# DMB.net
KiCad netlist of a schematic drawn in Altium Designer
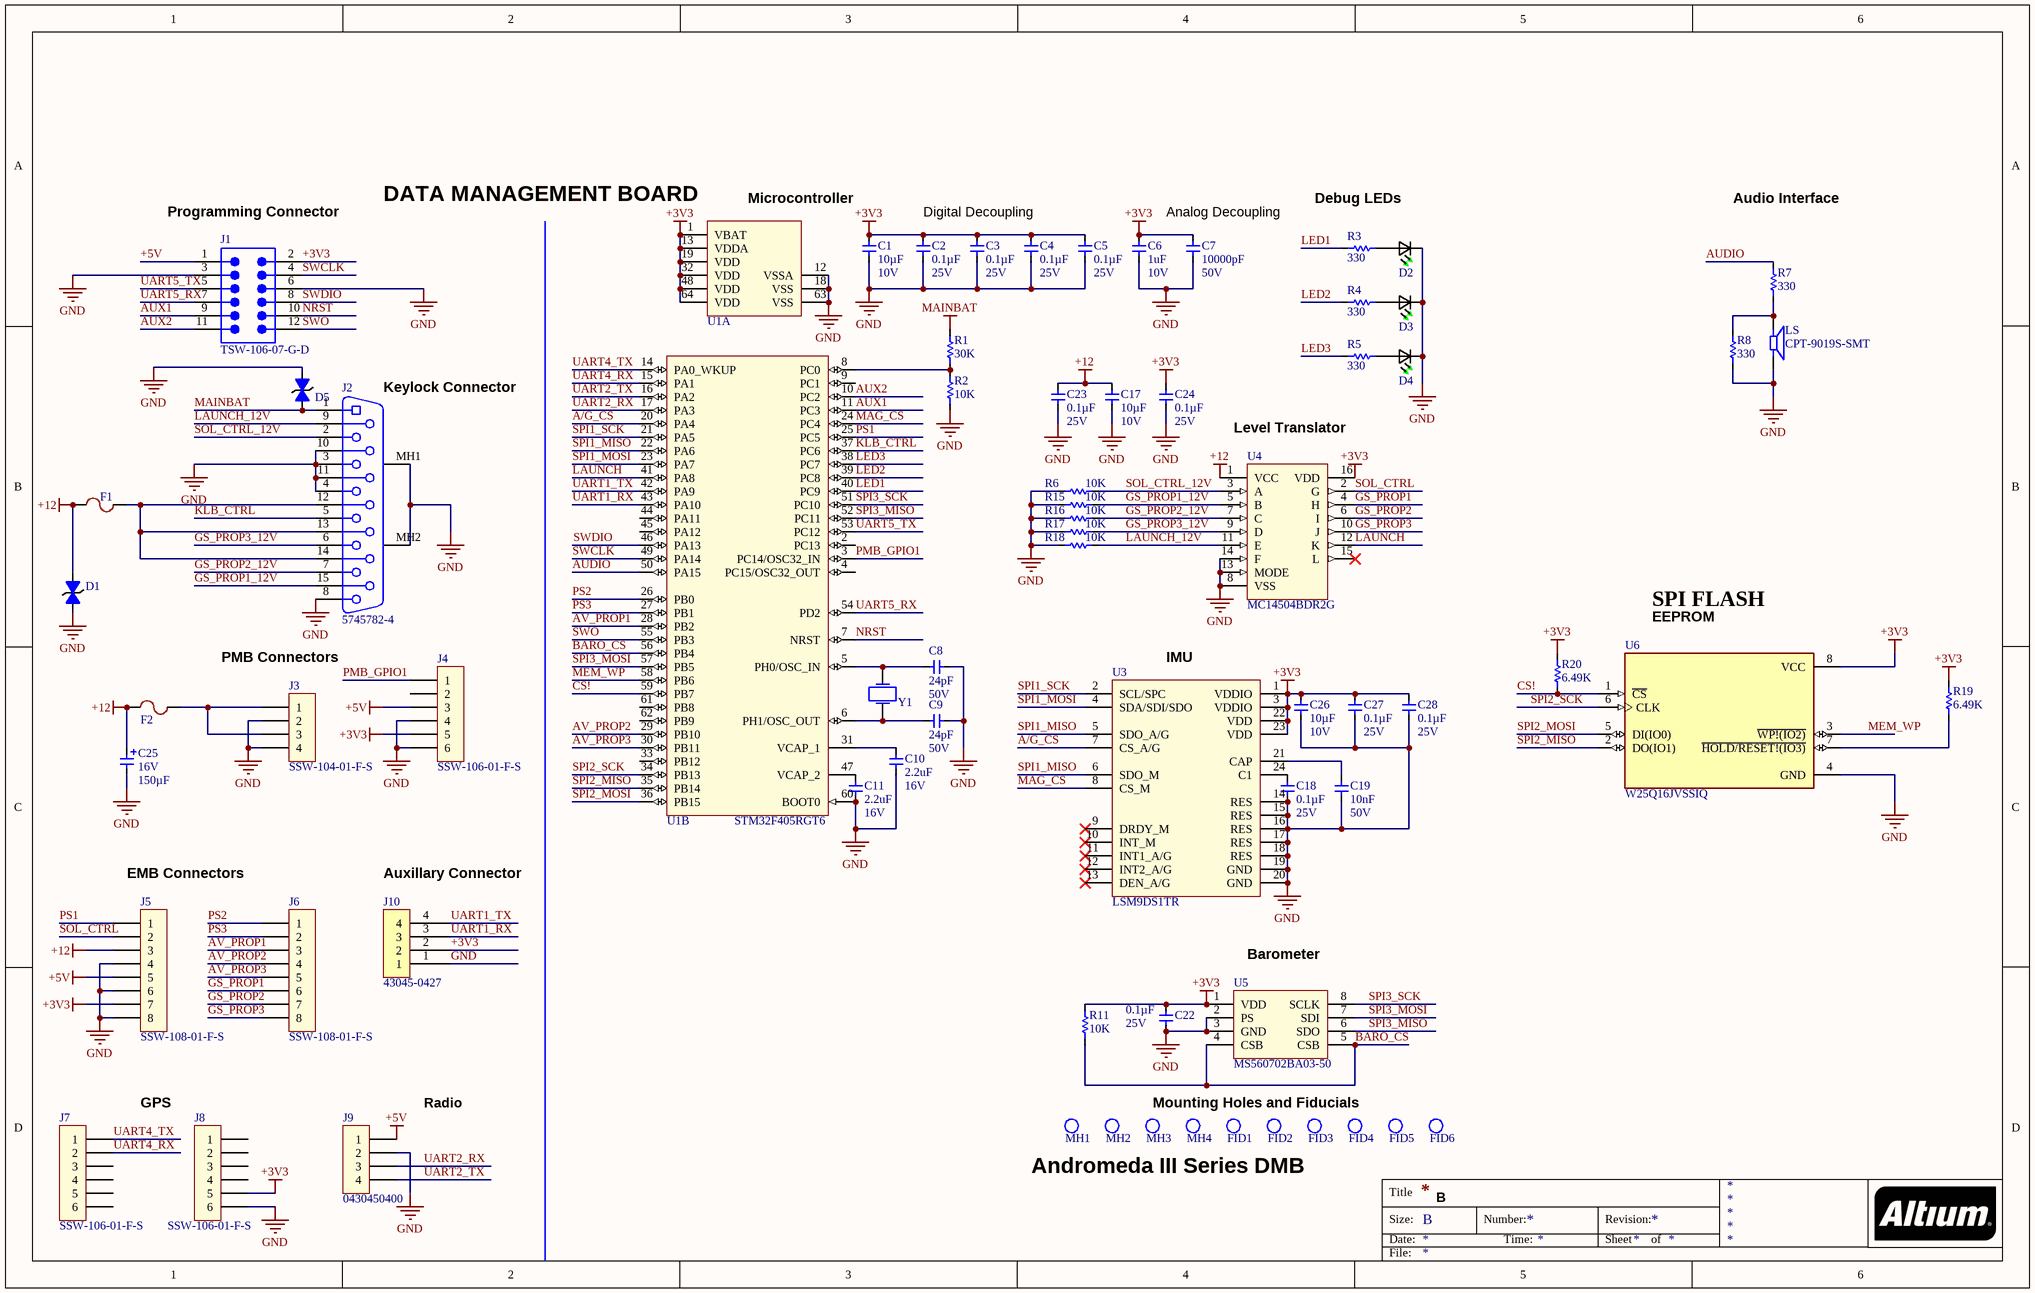
[diagram p0: DMB.SchDoc]

(export (version "E")
  (design (tool "Eeschema 10.0.6"))
  (components
    (comp (ref "C1")
      (value "CL10A106MP8NNNC")
      (footprint "0603[1608]")
      (description "CAP CER 10UF 10V X5R 0603")
      (fields
        (field (name "MANUFACTURER") "Samsung Electro-Mechanics")
        (field (name "TOLERANCE") "±20%")
        (field (name "CAPACITANCE") "10µF")
        (field (name "VOLTAGE - RATED") "10V")
      )
      (libsource (lib "SOARSchematics") (part "CL10A106MP8NNNC"))
    )
    (comp (ref "C2")
      (value "CGA3E2X7R1E104K080AA")
      (footprint "0603[1608]")
      (description "CAP CER 0.1UF 25V X7R 0603")
      (fields
        (field (name "MANUFACTURER") "TDK Corporation")
        (field (name "TOLERANCE") "±10%")
        (field (name "CAPACITANCE") "0.1µF")
        (field (name "VOLTAGE - RATED") "25V")
      )
      (libsource (lib "SOARSchematics") (part "CGA3E2X7R1E104K080AA"))
    )
    (comp (ref "C3")
      (value "CGA3E2X7R1E104K080AA")
      (footprint "0603[1608]")
      (description "CAP CER 0.1UF 25V X7R 0603")
      (fields
        (field (name "MANUFACTURER") "TDK Corporation")
        (field (name "TOLERANCE") "±10%")
        (field (name "CAPACITANCE") "0.1µF")
        (field (name "VOLTAGE - RATED") "25V")
      )
      (libsource (lib "SOARSchematics") (part "CGA3E2X7R1E104K080AA"))
    )
    (comp (ref "C4")
      (value "CGA3E2X7R1E104K080AA")
      (footprint "0603[1608]")
      (description "CAP CER 0.1UF 25V X7R 0603")
      (fields
        (field (name "MANUFACTURER") "TDK Corporation")
        (field (name "TOLERANCE") "±10%")
        (field (name "CAPACITANCE") "0.1µF")
        (field (name "VOLTAGE - RATED") "25V")
      )
      (libsource (lib "SOARSchematics") (part "CGA3E2X7R1E104K080AA"))
    )
    (comp (ref "C5")
      (value "CGA3E2X7R1E104K080AA")
      (footprint "0603[1608]")
      (description "CAP CER 0.1UF 25V X7R 0603")
      (fields
        (field (name "MANUFACTURER") "TDK Corporation")
        (field (name "TOLERANCE") "±10%")
        (field (name "CAPACITANCE") "0.1µF")
        (field (name "VOLTAGE - RATED") "25V")
      )
      (libsource (lib "SOARSchematics") (part "CGA3E2X7R1E104K080AA"))
    )
    (comp (ref "C6")
      (value "CL10A105KP8NNNC")
      (footprint "0603[1608]")
      (description "CAP CER 1UF 10V X5R 0603")
      (fields
        (field (name "MANUFACTURER") "Samsung Electro-Mechanics")
        (field (name "TOLERANCE") "±10%")
        (field (name "CAPACITANCE") "1uF")
        (field (name "VOLTAGE - RATED") "10V")
      )
      (libsource (lib "SOARSchematics") (part "CL10A105KP8NNNC"))
    )
    (comp (ref "C7")
      (value "CGA3E2X7R1H103K080AA")
      (footprint "0603[1608]")
      (description "CAP CER 10000PF 50V X7R 0603")
      (fields
        (field (name "MANUFACTURER") "TDK Corporation")
        (field (name "TOLERANCE") "±10%")
        (field (name "CAPACITANCE") "10000pF")
        (field (name "VOLTAGE - RATED") "50V")
      )
      (libsource (lib "SOARSchematics") (part "CGA3E2X7R1H103K080AA"))
    )
    (comp (ref "C8")
      (value "06035A240JAT2A")
      (footprint "0603[1608]")
      (description "CAP CER 24PF 50V NP0 0603")
      (fields
        (field (name "MANUFACTURER") "AVX Corporation")
        (field (name "TOLERANCE") "±5%")
        (field (name "CAPACITANCE") "24pF")
        (field (name "VOLTAGE - RATED") "50V")
      )
      (libsource (lib "SOARSchematics") (part "06035A240JAT2A"))
    )
    (comp (ref "C9")
      (value "06035A240JAT2A")
      (footprint "0603[1608]")
      (description "CAP CER 24PF 50V NP0 0603")
      (fields
        (field (name "MANUFACTURER") "AVX Corporation")
        (field (name "TOLERANCE") "±5%")
        (field (name "CAPACITANCE") "24pF")
        (field (name "VOLTAGE - RATED") "50V")
      )
      (libsource (lib "SOARSchematics") (part "06035A240JAT2A"))
    )
    (comp (ref "C10")
      (value "C1608X5R1C225K080AB")
      (footprint "0603[1608]")
      (description "CAP CER 2.2UF 16V X5R 0603")
      (fields
        (field (name "MANUFACTURER") "TDK Corporation")
        (field (name "TOLERANCE") "±10%")
        (field (name "CAPACITANCE") "2.2uF")
        (field (name "VOLTAGE - RATED") "16V")
      )
      (libsource (lib "SOARSchematics") (part "C1608X5R1C225K080AB"))
    )
    (comp (ref "C11")
      (value "C1608X5R1C225K080AB")
      (footprint "0603[1608]")
      (description "CAP CER 2.2UF 16V X5R 0603")
      (fields
        (field (name "MANUFACTURER") "TDK Corporation")
        (field (name "TOLERANCE") "±10%")
        (field (name "CAPACITANCE") "2.2uF")
        (field (name "VOLTAGE - RATED") "16V")
      )
      (libsource (lib "SOARSchematics") (part "C1608X5R1C225K080AB"))
    )
    (comp (ref "C17")
      (value "CL10A106MP8NNNC")
      (footprint "0603[1608]")
      (description "CAP CER 10UF 10V X5R 0603")
      (fields
        (field (name "MANUFACTURER") "Samsung Electro-Mechanics")
        (field (name "TOLERANCE") "±20%")
        (field (name "CAPACITANCE") "10µF")
        (field (name "VOLTAGE - RATED") "10V")
      )
      (libsource (lib "SOARSchematics") (part "CL10A106MP8NNNC"))
    )
    (comp (ref "C18")
      (value "CGA3E2X7R1E104K080AA")
      (footprint "0603[1608]")
      (description "CAP CER 0.1UF 25V X7R 0603")
      (fields
        (field (name "MANUFACTURER") "TDK Corporation")
        (field (name "TOLERANCE") "±10%")
        (field (name "CAPACITANCE") "0.1µF")
        (field (name "VOLTAGE - RATED") "25V")
      )
      (libsource (lib "SOARSchematics") (part "CGA3E2X7R1E104K080AA"))
    )
    (comp (ref "C19")
      (value "GRM1885C1H103JA01D")
      (footprint "0603[1608]")
      (description "CAP CER 10000PF 50V C0G/NP0 0603")
      (fields
        (field (name "MANUFACTURER") "Murata Electronics")
        (field (name "TOLERANCE") "±50%")
        (field (name "CAPACITANCE") "10nF")
        (field (name "VOLTAGE - RATED") "50V")
      )
      (libsource (lib "SOARSchematics") (part "GRM1885C1H103JA01D"))
    )
    (comp (ref "C22")
      (value "CGA3E2X7R1E104K080AA")
      (footprint "0603[1608]")
      (description "CAP CER 0.1UF 25V X7R 0603")
      (fields
        (field (name "MANUFACTURER") "TDK Corporation")
        (field (name "TOLERANCE") "±10%")
        (field (name "CAPACITANCE") "0.1µF")
        (field (name "VOLTAGE - RATED") "25V")
      )
      (libsource (lib "SOARSchematics") (part "CGA3E2X7R1E104K080AA"))
    )
    (comp (ref "C23")
      (value "CGA3E2X7R1E104K080AA")
      (footprint "0603[1608]")
      (description "CAP CER 0.1UF 25V X7R 0603")
      (fields
        (field (name "MANUFACTURER") "TDK Corporation")
        (field (name "TOLERANCE") "±10%")
        (field (name "CAPACITANCE") "0.1µF")
        (field (name "VOLTAGE - RATED") "25V")
      )
      (libsource (lib "SOARSchematics") (part "CGA3E2X7R1E104K080AA"))
    )
    (comp (ref "C24")
      (value "CGA3E2X7R1E104K080AA")
      (footprint "0603[1608]")
      (description "CAP CER 0.1UF 25V X7R 0603")
      (fields
        (field (name "MANUFACTURER") "TDK Corporation")
        (field (name "TOLERANCE") "±10%")
        (field (name "CAPACITANCE") "0.1µF")
        (field (name "VOLTAGE - RATED") "25V")
      )
      (libsource (lib "SOARSchematics") (part "CGA3E2X7R1E104K080AA"))
    )
    (comp (ref "C25")
      (value "TAJD157K016RNJ")
      (footprint "TAJD157K016RNJ")
      (description "CAP TANT 150UF 10% 16V 2917")
      (fields
        (field (name "MANUFACTURER") "AVX Corporation")
        (field (name "TOLERANCE") "±10%")
        (field (name "VOLTAGE - RATED") "16V")
        (field (name "CAPACITANCE") "150µF")
      )
      (libsource (lib "SOARSchematics") (part "TAJD157K016RNJ"))
    )
    (comp (ref "C26")
      (value "CL10A106MP8NNNC")
      (footprint "0603[1608]")
      (description "CAP CER 10UF 10V X5R 0603")
      (fields
        (field (name "MANUFACTURER") "Samsung Electro-Mechanics")
        (field (name "TOLERANCE") "±20%")
        (field (name "CAPACITANCE") "10µF")
        (field (name "VOLTAGE - RATED") "10V")
      )
      (libsource (lib "SOARSchematics") (part "CL10A106MP8NNNC"))
    )
    (comp (ref "C27")
      (value "CGA3E2X7R1E104K080AA")
      (footprint "0603[1608]")
      (description "CAP CER 0.1UF 25V X7R 0603")
      (fields
        (field (name "MANUFACTURER") "TDK Corporation")
        (field (name "TOLERANCE") "±10%")
        (field (name "CAPACITANCE") "0.1µF")
        (field (name "VOLTAGE - RATED") "25V")
      )
      (libsource (lib "SOARSchematics") (part "CGA3E2X7R1E104K080AA"))
    )
    (comp (ref "C28")
      (value "CGA3E2X7R1E104K080AA")
      (footprint "0603[1608]")
      (description "CAP CER 0.1UF 25V X7R 0603")
      (fields
        (field (name "MANUFACTURER") "TDK Corporation")
        (field (name "TOLERANCE") "±10%")
        (field (name "CAPACITANCE") "0.1µF")
        (field (name "VOLTAGE - RATED") "25V")
      )
      (libsource (lib "SOARSchematics") (part "CGA3E2X7R1E104K080AA"))
    )
    (comp (ref "D1")
      (value "CDSOD323-T12C")
      (footprint "CDSOD323-T12C")
      (description "TVS DIODE 12V 28.3V SOD323")
      (fields (field (name "MANUFACTURER") "Bourns Inc."))
      (libsource (lib "SOARSchematics") (part "CDSOD323-T12C"))
    )
    (comp (ref "D2")
      (value "LTST-C191KGKT")
      (footprint "LTST-C191KGKT")
      (description "LED GREEN CLEAR SMD 0603")
      (fields (field (name "MANUFACTURER") "Lite-On Inc."))
      (libsource (lib "SOARSchematics") (part "LTST-C191KGKT"))
    )
    (comp (ref "D3")
      (value "LTST-C191KGKT")
      (footprint "LTST-C191KGKT")
      (description "LED GREEN CLEAR SMD 0603")
      (fields (field (name "MANUFACTURER") "Lite-On Inc."))
      (libsource (lib "SOARSchematics") (part "LTST-C191KGKT"))
    )
    (comp (ref "D4")
      (value "LTST-C191KGKT")
      (footprint "LTST-C191KGKT")
      (description "LED GREEN CLEAR SMD 0603")
      (fields (field (name "MANUFACTURER") "Lite-On Inc."))
      (libsource (lib "SOARSchematics") (part "LTST-C191KGKT"))
    )
    (comp (ref "D5")
      (value "CDSOD323-T12C")
      (footprint "CDSOD323-T12C")
      (description "TVS DIODE 12V 28.3V SOD323")
      (fields (field (name "MANUFACTURER") "Bourns Inc."))
      (libsource (lib "SOARSchematics") (part "CDSOD323-T12C"))
    )
    (comp (ref "F1")
      (value "SF-0603FP500M-2")
      (footprint "SF-0603FP500M-2")
      (description "FUSE BOARD MOUNT 5A 32VDC 0603")
      (fields (field (name "MANUFACTURER") "Bourns Inc."))
      (libsource (lib "SOARSchematics") (part "SF-0603FP500M-2"))
    )
    (comp (ref "F2")
      (value "SF-0603FP500M-2")
      (footprint "SF-0603FP500M-2")
      (description "FUSE BOARD MOUNT 5A 32VDC 0603")
      (fields (field (name "MANUFACTURER") "Bourns Inc."))
      (libsource (lib "SOARSchematics") (part "SF-0603FP500M-2"))
    )
    (comp (ref "FID1")
      (value "FID_1MM_ROUND_SL")
      (footprint "FID_1MM_ROUND_SL")
      (description "Fiducial 1mm Round Single Layer")
      (libsource (lib "SOARSchematics") (part "FID_1MM_ROUND_SL"))
    )
    (comp (ref "FID2")
      (value "FID_1MM_ROUND_SL")
      (footprint "FID_1MM_ROUND_SL")
      (description "Fiducial 1mm Round Single Layer")
      (libsource (lib "SOARSchematics") (part "FID_1MM_ROUND_SL"))
    )
    (comp (ref "FID3")
      (value "FID_1MM_ROUND_SL")
      (footprint "FID_1MM_ROUND_SL")
      (description "Fiducial 1mm Round Single Layer")
      (libsource (lib "SOARSchematics") (part "FID_1MM_ROUND_SL"))
    )
    (comp (ref "FID4")
      (value "FID_1MM_ROUND_SL")
      (footprint "FID_1MM_ROUND_SL")
      (description "Fiducial 1mm Round Single Layer")
      (libsource (lib "SOARSchematics") (part "FID_1MM_ROUND_SL"))
    )
    (comp (ref "FID5")
      (value "FID_1MM_ROUND_SL")
      (footprint "FID_1MM_ROUND_SL")
      (description "Fiducial 1mm Round Single Layer")
      (libsource (lib "SOARSchematics") (part "FID_1MM_ROUND_SL"))
    )
    (comp (ref "FID6")
      (value "FID_1MM_ROUND_SL")
      (footprint "FID_1MM_ROUND_SL")
      (description "Fiducial 1mm Round Single Layer")
      (libsource (lib "SOARSchematics") (part "FID_1MM_ROUND_SL"))
    )
    (comp (ref "J1")
      (value "TSW-106-07-G-D")
      (footprint "SMTC-TSW-106-07-X-D")
      (description "0.025\" SQ Post Header, Through-hole, Vertical, -55 to 125 degC, 2.54 mm Pitch, 12-Pin, Male, RoHS")
      (fields (field (name "MANUFACTURER") "Samtec"))
      (libsource (lib "Altium Content Vault") (part "SMTC-TSW-106-07-X-D"))
    )
    (comp (ref "J2")
      (value "5745782-4")
      (footprint "TECO-5745782-4_V")
      (fields (field (name "MANUFACTURER") "TE Connectivity"))
      (libsource (lib "Altium Content Vault") (part "CN-2S-2F-D15"))
    )
    (comp (ref "J3")
      (value "SSW-104-01-F-S")
      (footprint "SSW-104-01-F-S")
      (description "CONN RCPT 4POS FEMALE 0.1 GOLD PCB")
      (fields (field (name "MANUFACTURER") "Samtec Inc."))
      (libsource (lib "SOARSchematics") (part "SSW-104-01-F-S"))
    )
    (comp (ref "J4")
      (value "SSW-106-01-F-S")
      (footprint "SSW-106-01-F-S")
      (description "CONN RCPT 6POS FEMALE 0.1 GOLD PCB")
      (fields (field (name "MANUFACTURER") "Samtec Inc."))
      (libsource (lib "") (part "SSW-106-01-F-S_1"))
    )
    (comp (ref "J5")
      (value "SSW-108-01-F-S")
      (footprint "SSW-108-01-F-S")
      (description "CONN RCPT 8POS FEMALE 0.1 GOLD PCB")
      (fields (field (name "MANUFACTURER") "Samtec Inc."))
      (libsource (lib "SOARSchematics") (part "SSW-108-01-F-S"))
    )
    (comp (ref "J6")
      (value "SSW-108-01-F-S")
      (footprint "SSW-108-01-F-S")
      (description "CONN RCPT 8POS FEMALE 0.1 GOLD PCB")
      (fields (field (name "MANUFACTURER") "Samtec Inc."))
      (libsource (lib "SOARSchematics") (part "SSW-108-01-F-S"))
    )
    (comp (ref "J7")
      (value "SSW-106-01-F-S")
      (footprint "SSW-106-01-F-S")
      (description "CONN RCPT 6POS FEMALE 0.1 GOLD PCB")
      (fields (field (name "MANUFACTURER") "Samtec Inc."))
      (libsource (lib "SOARSchematics") (part "SSW-106-01-F-S"))
    )
    (comp (ref "J8")
      (value "SSW-106-01-F-S")
      (footprint "SSW-106-01-F-S")
      (description "CONN RCPT 6POS FEMALE 0.1 GOLD PCB")
      (fields (field (name "MANUFACTURER") "Samtec Inc."))
      (libsource (lib "SOARSchematics") (part "SSW-106-01-F-S"))
    )
    (comp (ref "J9")
      (value "0430450400")
      (footprint "0430450400")
      (description "CONN HEADER R/A 4POS 3MM")
      (fields (field (name "MANUFACTURER") "Molex"))
      (libsource (lib "SOARSchematics") (part "0430450400"))
    )
    (comp (ref "J10")
      (value "43045-0427")
      (footprint "43045-0427")
      (libsource (lib "SOARSchematics") (part "43045-0427"))
    )
    (comp (ref "LS")
      (value "CPT-9019S-SMT")
      (footprint "CUI_CPT-9019S-SMT")
      (description "9 mm, 25 Vp-p Vdc, 65 dB, Surface Mount _SMT_, Piezo Audio Transducer Buzzer")
      (fields (field (name "MP") "CPT-9019S-SMT-TR") (field (name "MF") "CUI Devices"))
      (libsource (lib "CPT-9019S-SMT") (part "CPT-9019S-SMT"))
    )
    (comp (ref "MH1")
      (value "Mounting Hole")
      (footprint "MOUNT-HOLE")
      (description "#4 Screw, 0.116in Diameter")
      (libsource (lib "SOARSchematics") (part "Mounting Hole"))
    )
    (comp (ref "MH2")
      (value "Mounting Hole")
      (footprint "MOUNT-HOLE")
      (description "#4 Screw, 0.116in Diameter")
      (libsource (lib "SOARSchematics") (part "Mounting Hole"))
    )
    (comp (ref "MH3")
      (value "Mounting Hole")
      (footprint "MOUNT-HOLE")
      (description "#4 Screw, 0.116in Diameter")
      (libsource (lib "SOARSchematics") (part "Mounting Hole"))
    )
    (comp (ref "MH4")
      (value "Mounting Hole")
      (footprint "MOUNT-HOLE")
      (description "#4 Screw, 0.116in Diameter")
      (libsource (lib "SOARSchematics") (part "Mounting Hole"))
    )
    (comp (ref "R1")
      (value "RC0603FR-0730KL")
      (footprint "0603[1608]")
      (description "RES SMD 30K OHM 1% 1/10W 0603")
      (fields
        (field (name "TOLERANCE") "±1%")
        (field (name "MANUFACTURER") "Yageo")
        (field (name "RESISTANCE") "30K")
      )
      (libsource (lib "SOARSchematics") (part "RC0603FR-0730KL"))
    )
    (comp (ref "R2")
      (value "ERJ-3GEYJ103V")
      (footprint "0603[1608]")
      (description "RES SMD 10K OHM 5% 1/10W 0603")
      (fields
        (field (name "TOLERANCE") "±5%")
        (field (name "MANUFACTURER") "Panasonic Electronic Components")
        (field (name "RESISTANCE") "10K")
      )
      (libsource (lib "SOARSchematics") (part "ERJ-3GEYJ103V"))
    )
    (comp (ref "R3")
      (value "RC1608F331CS")
      (footprint "0603[1608]")
      (description "RES SMD 330 OHM 1% 1/10W 0603")
      (fields
        (field (name "TOLERANCE") "±1%")
        (field (name "MANUFACTURER") "Samsung Electro-Mechanics")
        (field (name "RESISTANCE") "330")
      )
      (libsource (lib "SOARSchematics") (part "RC1608F331CS"))
    )
    (comp (ref "R4")
      (value "RC1608F331CS")
      (footprint "0603[1608]")
      (description "RES SMD 330 OHM 1% 1/10W 0603")
      (fields
        (field (name "TOLERANCE") "±1%")
        (field (name "MANUFACTURER") "Samsung Electro-Mechanics")
        (field (name "RESISTANCE") "330")
      )
      (libsource (lib "SOARSchematics") (part "RC1608F331CS"))
    )
    (comp (ref "R5")
      (value "RC1608F331CS")
      (footprint "0603[1608]")
      (description "RES SMD 330 OHM 1% 1/10W 0603")
      (fields
        (field (name "TOLERANCE") "±1%")
        (field (name "MANUFACTURER") "Samsung Electro-Mechanics")
        (field (name "RESISTANCE") "330")
      )
      (libsource (lib "SOARSchematics") (part "RC1608F331CS"))
    )
    (comp (ref "R6")
      (value "ERJ-3GEYJ103V")
      (footprint "0603[1608]")
      (description "RES SMD 10K OHM 5% 1/10W 0603")
      (fields
        (field (name "TOLERANCE") "±5%")
        (field (name "MANUFACTURER") "Panasonic Electronic Components")
        (field (name "RESISTANCE") "10K")
      )
      (libsource (lib "SOARSchematics") (part "ERJ-3GEYJ103V"))
    )
    (comp (ref "R7")
      (value "RC1608F331CS")
      (footprint "0603[1608]")
      (description "RES SMD 330 OHM 1% 1/10W 0603")
      (fields
        (field (name "TOLERANCE") "±1%")
        (field (name "MANUFACTURER") "Samsung Electro-Mechanics")
        (field (name "RESISTANCE") "330")
      )
      (libsource (lib "SOARSchematics") (part "RC1608F331CS"))
    )
    (comp (ref "R8")
      (value "RC1608F331CS")
      (footprint "0603[1608]")
      (description "RES SMD 330 OHM 1% 1/10W 0603")
      (fields
        (field (name "TOLERANCE") "±1%")
        (field (name "MANUFACTURER") "Samsung Electro-Mechanics")
        (field (name "RESISTANCE") "330")
      )
      (libsource (lib "SOARSchematics") (part "RC1608F331CS"))
    )
    (comp (ref "R11")
      (value "ERJ-3GEYJ103V")
      (footprint "0603[1608]")
      (description "RES SMD 10K OHM 5% 1/10W 0603")
      (fields
        (field (name "TOLERANCE") "±5%")
        (field (name "MANUFACTURER") "Panasonic Electronic Components")
        (field (name "RESISTANCE") "10K")
      )
      (libsource (lib "SOARSchematics") (part "ERJ-3GEYJ103V"))
    )
    (comp (ref "R15")
      (value "ERJ-3GEYJ103V")
      (footprint "0603[1608]")
      (description "RES SMD 10K OHM 5% 1/10W 0603")
      (fields
        (field (name "TOLERANCE") "±5%")
        (field (name "MANUFACTURER") "Panasonic Electronic Components")
        (field (name "RESISTANCE") "10K")
      )
      (libsource (lib "SOARSchematics") (part "ERJ-3GEYJ103V"))
    )
    (comp (ref "R16")
      (value "ERJ-3GEYJ103V")
      (footprint "0603[1608]")
      (description "RES SMD 10K OHM 5% 1/10W 0603")
      (fields
        (field (name "TOLERANCE") "±5%")
        (field (name "MANUFACTURER") "Panasonic Electronic Components")
        (field (name "RESISTANCE") "10K")
      )
      (libsource (lib "SOARSchematics") (part "ERJ-3GEYJ103V"))
    )
    (comp (ref "R17")
      (value "ERJ-3GEYJ103V")
      (footprint "0603[1608]")
      (description "RES SMD 10K OHM 5% 1/10W 0603")
      (fields
        (field (name "TOLERANCE") "±5%")
        (field (name "MANUFACTURER") "Panasonic Electronic Components")
        (field (name "RESISTANCE") "10K")
      )
      (libsource (lib "SOARSchematics") (part "ERJ-3GEYJ103V"))
    )
    (comp (ref "R18")
      (value "ERJ-3GEYJ103V")
      (footprint "0603[1608]")
      (description "RES SMD 10K OHM 5% 1/10W 0603")
      (fields
        (field (name "TOLERANCE") "±5%")
        (field (name "MANUFACTURER") "Panasonic Electronic Components")
        (field (name "RESISTANCE") "10K")
      )
      (libsource (lib "SOARSchematics") (part "ERJ-3GEYJ103V"))
    )
    (comp (ref "R19")
      (value "RT0603DRE076K49L")
      (footprint "0603[1608]")
      (description "RES SMD 6.49KOHM 0.5% 1/10W 0603")
      (fields
        (field (name "TOLERANCE") "±0.5%")
        (field (name "MANUFACTURER") "Yageo")
        (field (name "RESISTANCE") "6.49K")
      )
      (libsource (lib "SOARSchematics") (part "RT0603DRE076K49L"))
    )
    (comp (ref "R20")
      (value "RT0603DRE076K49L")
      (footprint "0603[1608]")
      (description "RES SMD 6.49KOHM 0.5% 1/10W 0603")
      (fields
        (field (name "TOLERANCE") "±0.5%")
        (field (name "MANUFACTURER") "Yageo")
        (field (name "RESISTANCE") "6.49K")
      )
      (libsource (lib "SOARSchematics") (part "RT0603DRE076K49L"))
    )
    (comp (ref "U1")
      (value "STM32F405RGT6")
      (footprint "TSQFP50P1200X1200X160-64N")
      (description "IC MCU 32BIT 1MB FLASH 64LQFP")
      (fields (field (name "MANUFACTURER") "STMicroelectronics"))
      (libsource (lib "SOARSchematics") (part "STM32F405RGT6"))
    )
    (comp (ref "U3")
      (value "LSM9DS1TR")
      (footprint "LSM9DS1TR")
      (description "IMU ACCEL/GYRO/MAG I2C/SPI 24LGA")
      (fields (field (name "MANUFACTURER") "STMicroelectronics"))
      (libsource (lib "SOARSchematics") (part "LSM9DS1TR"))
    )
    (comp (ref "U4")
      (value "MC14504BDR2G")
      (footprint "MC14504BDR2G")
      (description "IC TRNSLTR UNIDIRECTIONAL 16SOIC")
      (fields (field (name "MANUFACTURER") "ON Semiconductor"))
      (libsource (lib "SOARSchematics") (part "MC14504BDR2G"))
    )
    (comp (ref "U5")
      (value "MS560702BA03-50")
      (footprint "MS560702BA03-50")
      (description "BAROMETRIC PRESSURE SENSOR")
      (fields
        (field (name "DIGI-KEY PART NUMBER") "223-1198-1-ND")
        (field (name "MANUFACTURER") "TE Connectivity Measurement Specialties")
      )
      (libsource (lib "SOARSchematics") (part "MS560702BA03-50"))
    )
    (comp (ref "U6")
      (value "W25Q16JVSSIQ")
      (footprint "W25Q16JVSSIQ")
      (description "FLASH - NOR Memory IC 16Mb _2M x 8_ SPI - Quad I/O 133MHz 8-SOIC")
      (fields (field (name "MF") "Winbond Electronics"))
      (libsource (lib "SOARSchematics") (part "W25Q16JVSSIQ"))
    )
    (comp (ref "Y1")
      (value "ABLS-8.000MHZ-B2-T")
      (footprint "ABLS-8.000MHZ-B2-T")
      (description "CRYSTAL 8.0000MHZ 18PF SMD")
      (fields (field (name "MANUFACTURER") "Abracon LLC"))
      (libsource (lib "SOARSchematics") (part "ABLS-8.000MHZ-B2-T"))
    )
  )
  (nets
    (net (code "1") (name "+3V3") (class "Default")
      (node (ref "C1") (pin "2") (pinfunction "2_2") (pintype "passive"))
      (node (ref "C2") (pin "2") (pinfunction "2_2") (pintype "passive"))
      (node (ref "C22") (pin "2") (pinfunction "2_2") (pintype "passive"))
      (node (ref "C24") (pin "2") (pinfunction "2_2") (pintype "passive"))
      (node (ref "C26") (pin "2") (pinfunction "2_2") (pintype "passive"))
      (node (ref "C27") (pin "2") (pinfunction "2_2") (pintype "passive"))
      (node (ref "C28") (pin "2") (pinfunction "2_2") (pintype "passive"))
      (node (ref "C3") (pin "2") (pinfunction "2_2") (pintype "passive"))
      (node (ref "C4") (pin "2") (pinfunction "2_2") (pintype "passive"))
      (node (ref "C5") (pin "2") (pinfunction "2_2") (pintype "passive"))
      (node (ref "C6") (pin "2") (pinfunction "2_2") (pintype "passive"))
      (node (ref "C7") (pin "2") (pinfunction "2_2") (pintype "passive"))
      (node (ref "J1") (pin "2") (pinfunction "2_2") (pintype "passive"))
      (node (ref "J10") (pin "2") (pinfunction "2_2") (pintype "passive"))
      (node (ref "J4") (pin "5") (pinfunction "5_5") (pintype "passive"))
      (node (ref "J5") (pin "7") (pinfunction "7_7") (pintype "passive"))
      (node (ref "J8") (pin "5") (pinfunction "5_5") (pintype "passive"))
      (node (ref "R11") (pin "2") (pinfunction "2_2") (pintype "passive"))
      (node (ref "R19") (pin "2") (pinfunction "2_2") (pintype "passive"))
      (node (ref "R20") (pin "2") (pinfunction "2_2") (pintype "passive"))
      (node (ref "U1") (pin "1") (pinfunction "VBAT_1") (pintype "power_in"))
      (node (ref "U1") (pin "13") (pinfunction "VDDA_13") (pintype "power_in"))
      (node (ref "U1") (pin "19") (pinfunction "VDD_19") (pintype "power_in"))
      (node (ref "U1") (pin "32") (pinfunction "VDD_32") (pintype "power_in"))
      (node (ref "U1") (pin "48") (pinfunction "VDD_48") (pintype "power_in"))
      (node (ref "U1") (pin "64") (pinfunction "VDD_64") (pintype "power_in"))
      (node (ref "U3") (pin "1") (pinfunction "VDDIO_1") (pintype "power_in"))
      (node (ref "U3") (pin "22") (pinfunction "VDD_22") (pintype "power_in"))
      (node (ref "U3") (pin "23") (pinfunction "VDD_23") (pintype "power_in"))
      (node (ref "U3") (pin "3") (pinfunction "VDDIO_3") (pintype "power_in"))
      (node (ref "U4") (pin "16") (pinfunction "VDD_16") (pintype "power_in"))
      (node (ref "U5") (pin "1") (pinfunction "VDD_1") (pintype "power_in"))
      (node (ref "U6") (pin "8") (pinfunction "VCC_8") (pintype "power_in"))
    )
    (net (code "2") (name "+5V") (class "Default")
      (node (ref "J1") (pin "1") (pinfunction "1_1") (pintype "passive"))
      (node (ref "J4") (pin "3") (pinfunction "3_3") (pintype "passive"))
      (node (ref "J5") (pin "5") (pinfunction "5_5") (pintype "passive"))
      (node (ref "J9") (pin "1") (pinfunction "1_1") (pintype "passive"))
    )
    (net (code "3") (name "+12") (class "Default")
      (node (ref "C17") (pin "2") (pinfunction "2_2") (pintype "passive"))
      (node (ref "C23") (pin "2") (pinfunction "2_2") (pintype "passive"))
      (node (ref "C25") (pin "1") (pinfunction "1_1") (pintype "passive"))
      (node (ref "D1") (pin "1") (pinfunction "1_1") (pintype "power_in"))
      (node (ref "F1") (pin "1") (pinfunction "1_1") (pintype "passive"))
      (node (ref "F2") (pin "1") (pinfunction "1_1") (pintype "passive"))
      (node (ref "J5") (pin "3") (pinfunction "3_3") (pintype "passive"))
      (node (ref "U4") (pin "1") (pinfunction "VCC_1") (pintype "power_in"))
    )
    (net (code "5") (name "/AUDIO") (class "Default")
      (node (ref "R7") (pin "1") (pinfunction "1_1") (pintype "passive"))
      (node (ref "U1") (pin "50") (pinfunction "PA15_50") (pintype "bidirectional"))
    )
    (net (code "6") (name "/AUX1") (class "Default")
      (node (ref "J1") (pin "9") (pinfunction "9_9") (pintype "passive"))
      (node (ref "U1") (pin "11") (pinfunction "PC3_11") (pintype "bidirectional"))
    )
    (net (code "7") (name "/AUX2") (class "Default")
      (node (ref "J1") (pin "11") (pinfunction "11_11") (pintype "passive"))
      (node (ref "U1") (pin "10") (pinfunction "PC2_10") (pintype "bidirectional"))
    )
    (net (code "8") (name "/AV_PROP1") (class "Default")
      (node (ref "J6") (pin "3") (pinfunction "3_3") (pintype "passive"))
      (node (ref "U1") (pin "28") (pinfunction "PB2_28") (pintype "bidirectional"))
    )
    (net (code "9") (name "/AV_PROP2") (class "Default")
      (node (ref "J6") (pin "4") (pinfunction "4_4") (pintype "passive"))
      (node (ref "U1") (pin "29") (pinfunction "PB10_29") (pintype "bidirectional"))
    )
    (net (code "10") (name "/AV_PROP3") (class "Default")
      (node (ref "J6") (pin "5") (pinfunction "5_5") (pintype "passive"))
      (node (ref "U1") (pin "30") (pinfunction "PB11_30") (pintype "bidirectional"))
    )
    (net (code "11") (name "/A{slash}G_~{CS}") (class "Default")
      (node (ref "U1") (pin "20") (pinfunction "PA4_20") (pintype "bidirectional"))
      (node (ref "U3") (pin "7") (pinfunction "CS_A/G_7") (pintype "passive"))
    )
    (net (code "12") (name "/BARO_~{CS}") (class "Default")
      (node (ref "R11") (pin "1") (pinfunction "1_1") (pintype "passive"))
      (node (ref "U1") (pin "56") (pinfunction "PB4_56") (pintype "bidirectional"))
      (node (ref "U5") (pin "4") (pinfunction "CSB_4") (pintype "passive"))
      (node (ref "U5") (pin "5") (pinfunction "CSB_5") (pintype "passive"))
    )
    (net (code "13") (name "/CS!") (class "Default")
      (node (ref "R20") (pin "1") (pinfunction "1_1") (pintype "passive"))
      (node (ref "U1") (pin "59") (pinfunction "PB7_59") (pintype "bidirectional"))
      (node (ref "U6") (pin "1") (pinfunction "~{CS}_1") (pintype "input"))
    )
    (net (code "14") (name "/GS_PROP1") (class "Default")
      (node (ref "J6") (pin "6") (pinfunction "6_6") (pintype "passive"))
      (node (ref "U4") (pin "4") (pinfunction "H_4") (pintype "output"))
    )
    (net (code "15") (name "/GS_PROP1_12V") (class "Default")
      (node (ref "J2") (pin "15") (pinfunction "15_15") (pintype "passive"))
      (node (ref "R15") (pin "2") (pinfunction "2_2") (pintype "passive"))
      (node (ref "U4") (pin "5") (pinfunction "B_5") (pintype "input"))
    )
    (net (code "16") (name "/GS_PROP2") (class "Default")
      (node (ref "J6") (pin "7") (pinfunction "7_7") (pintype "passive"))
      (node (ref "U4") (pin "6") (pinfunction "I_6") (pintype "output"))
    )
    (net (code "17") (name "/GS_PROP2_12V") (class "Default")
      (node (ref "J2") (pin "7") (pinfunction "7_7") (pintype "passive"))
      (node (ref "R16") (pin "2") (pinfunction "2_2") (pintype "passive"))
      (node (ref "U4") (pin "7") (pinfunction "C_7") (pintype "input"))
    )
    (net (code "18") (name "/GS_PROP3") (class "Default")
      (node (ref "J6") (pin "8") (pinfunction "8_8") (pintype "passive"))
      (node (ref "U4") (pin "10") (pinfunction "J_10") (pintype "output"))
    )
    (net (code "19") (name "/GS_PROP3_12V") (class "Default")
      (node (ref "J2") (pin "6") (pinfunction "6_6") (pintype "passive"))
      (node (ref "R17") (pin "2") (pinfunction "2_2") (pintype "passive"))
      (node (ref "U4") (pin "9") (pinfunction "D_9") (pintype "input"))
    )
    (net (code "20") (name "/KLB_CTRL") (class "Default")
      (node (ref "J2") (pin "5") (pinfunction "5_5") (pintype "passive"))
      (node (ref "U1") (pin "37") (pinfunction "PC6_37") (pintype "bidirectional"))
    )
    (net (code "21") (name "/LAUNCH") (class "Default")
      (node (ref "U1") (pin "41") (pinfunction "PA8_41") (pintype "bidirectional"))
      (node (ref "U4") (pin "12") (pinfunction "K_12") (pintype "output"))
    )
    (net (code "22") (name "/LAUNCH_12V") (class "Default")
      (node (ref "J2") (pin "9") (pinfunction "9_9") (pintype "passive"))
      (node (ref "R18") (pin "2") (pinfunction "2_2") (pintype "passive"))
      (node (ref "U4") (pin "11") (pinfunction "E_11") (pintype "input"))
    )
    (net (code "23") (name "/LED1") (class "Default")
      (node (ref "R3") (pin "2") (pinfunction "2_2") (pintype "passive"))
      (node (ref "U1") (pin "40") (pinfunction "PC9_40") (pintype "bidirectional"))
    )
    (net (code "24") (name "/LED2") (class "Default")
      (node (ref "R4") (pin "2") (pinfunction "2_2") (pintype "passive"))
      (node (ref "U1") (pin "39") (pinfunction "PC8_39") (pintype "bidirectional"))
    )
    (net (code "25") (name "/LED3") (class "Default")
      (node (ref "R5") (pin "2") (pinfunction "2_2") (pintype "passive"))
      (node (ref "U1") (pin "38") (pinfunction "PC7_38") (pintype "bidirectional"))
    )
    (net (code "26") (name "/MAG_~{CS}") (class "Default")
      (node (ref "U1") (pin "24") (pinfunction "PC4_24") (pintype "bidirectional"))
      (node (ref "U3") (pin "8") (pinfunction "CS_M_8") (pintype "passive"))
    )
    (net (code "27") (name "/MEM_WP") (class "Default")
      (node (ref "U1") (pin "58") (pinfunction "PB6_58") (pintype "bidirectional"))
      (node (ref "U6") (pin "3") (pinfunction "~{WP!(IO2)}_3") (pintype "bidirectional"))
    )
    (net (code "28") (name "/NRST") (class "Default")
      (node (ref "J1") (pin "10") (pinfunction "10_10") (pintype "passive"))
      (node (ref "U1") (pin "7") (pinfunction "NRST_7") (pintype "bidirectional"))
    )
    (net (code "29") (name "/PMB_GPIO1") (class "Default")
      (node (ref "J4") (pin "1") (pinfunction "1_1") (pintype "passive"))
      (node (ref "U1") (pin "3") (pinfunction "PC14/OSC32_IN_3") (pintype "bidirectional"))
    )
    (net (code "30") (name "/PS1") (class "Default")
      (node (ref "J5") (pin "1") (pinfunction "1_1") (pintype "passive"))
      (node (ref "U1") (pin "25") (pinfunction "PC5_25") (pintype "bidirectional"))
    )
    (net (code "31") (name "/PS2") (class "Default")
      (node (ref "J6") (pin "1") (pinfunction "1_1") (pintype "passive"))
      (node (ref "U1") (pin "26") (pinfunction "PB0_26") (pintype "bidirectional"))
    )
    (net (code "32") (name "/PS3") (class "Default")
      (node (ref "J6") (pin "2") (pinfunction "2_2") (pintype "passive"))
      (node (ref "U1") (pin "27") (pinfunction "PB1_27") (pintype "bidirectional"))
    )
    (net (code "33") (name "/SOL_CTRL") (class "Default")
      (node (ref "J5") (pin "2") (pinfunction "2_2") (pintype "passive"))
      (node (ref "U4") (pin "2") (pinfunction "G_2") (pintype "output"))
    )
    (net (code "34") (name "/SOL_CTRL_12V") (class "Default")
      (node (ref "J2") (pin "2") (pinfunction "2_2") (pintype "passive"))
      (node (ref "R6") (pin "2") (pinfunction "2_2") (pintype "passive"))
      (node (ref "U4") (pin "3") (pinfunction "A_3") (pintype "input"))
    )
    (net (code "35") (name "/SPI1_MISO") (class "Default")
      (node (ref "U1") (pin "22") (pinfunction "PA6_22") (pintype "bidirectional"))
      (node (ref "U3") (pin "5") (pinfunction "SDO_A/G_5") (pintype "passive"))
      (node (ref "U3") (pin "6") (pinfunction "SDO_M_6") (pintype "passive"))
    )
    (net (code "36") (name "/SPI1_MOSI") (class "Default")
      (node (ref "U1") (pin "23") (pinfunction "PA7_23") (pintype "bidirectional"))
      (node (ref "U3") (pin "4") (pinfunction "SDA/SDI/SDO_4") (pintype "passive"))
    )
    (net (code "37") (name "/SPI1_SCK") (class "Default")
      (node (ref "U1") (pin "21") (pinfunction "PA5_21") (pintype "bidirectional"))
      (node (ref "U3") (pin "2") (pinfunction "SCL/SPC_2") (pintype "passive"))
    )
    (net (code "38") (name "/SPI2_MISO") (class "Default")
      (node (ref "U1") (pin "35") (pinfunction "PB14_35") (pintype "bidirectional"))
      (node (ref "U6") (pin "2") (pinfunction "DO(IO1)_2") (pintype "bidirectional"))
    )
    (net (code "39") (name "/SPI2_MOSI") (class "Default")
      (node (ref "U1") (pin "36") (pinfunction "PB15_36") (pintype "bidirectional"))
      (node (ref "U6") (pin "5") (pinfunction "DI(IO0)_5") (pintype "bidirectional"))
    )
    (net (code "40") (name "/SPI2_SCK") (class "Default")
      (node (ref "U1") (pin "34") (pinfunction "PB13_34") (pintype "bidirectional"))
      (node (ref "U6") (pin "6") (pinfunction "CLK_6") (pintype "input"))
    )
    (net (code "41") (name "/SPI3_MISO") (class "Default")
      (node (ref "U1") (pin "52") (pinfunction "PC11_52") (pintype "bidirectional"))
      (node (ref "U5") (pin "6") (pinfunction "SDO_6") (pintype "passive"))
    )
    (net (code "42") (name "/SPI3_MOSI") (class "Default")
      (node (ref "U1") (pin "57") (pinfunction "PB5_57") (pintype "bidirectional"))
      (node (ref "U5") (pin "7") (pinfunction "SDI_7") (pintype "passive"))
    )
    (net (code "43") (name "/SPI3_SCK") (class "Default")
      (node (ref "U1") (pin "51") (pinfunction "PC10_51") (pintype "bidirectional"))
      (node (ref "U5") (pin "8") (pinfunction "SCLK_8") (pintype "passive"))
    )
    (net (code "44") (name "/SWCLK") (class "Default")
      (node (ref "J1") (pin "4") (pinfunction "4_4") (pintype "passive"))
      (node (ref "U1") (pin "49") (pinfunction "PA14_49") (pintype "bidirectional"))
    )
    (net (code "45") (name "/SWDIO") (class "Default")
      (node (ref "J1") (pin "8") (pinfunction "8_8") (pintype "passive"))
      (node (ref "U1") (pin "46") (pinfunction "PA13_46") (pintype "bidirectional"))
    )
    (net (code "46") (name "/SWO") (class "Default")
      (node (ref "J1") (pin "12") (pinfunction "12_12") (pintype "passive"))
      (node (ref "U1") (pin "55") (pinfunction "PB3_55") (pintype "bidirectional"))
    )
    (net (code "47") (name "/UART1_RX") (class "Default")
      (node (ref "J10") (pin "3") (pinfunction "3_3") (pintype "passive"))
      (node (ref "U1") (pin "43") (pinfunction "PA10_43") (pintype "bidirectional"))
    )
    (net (code "48") (name "/UART1_TX") (class "Default")
      (node (ref "J10") (pin "4") (pinfunction "4_4") (pintype "passive"))
      (node (ref "U1") (pin "42") (pinfunction "PA9_42") (pintype "bidirectional"))
    )
    (net (code "49") (name "/UART2_RX") (class "Default")
      (node (ref "J9") (pin "3") (pinfunction "3_3") (pintype "passive"))
      (node (ref "U1") (pin "17") (pinfunction "PA3_17") (pintype "bidirectional"))
    )
    (net (code "50") (name "/UART2_TX") (class "Default")
      (node (ref "J9") (pin "4") (pinfunction "4_4") (pintype "passive"))
      (node (ref "U1") (pin "16") (pinfunction "PA2_16") (pintype "bidirectional"))
    )
    (net (code "51") (name "/UART4_RX") (class "Default")
      (node (ref "J7") (pin "2") (pinfunction "2_2") (pintype "passive"))
      (node (ref "U1") (pin "15") (pinfunction "PA1_15") (pintype "bidirectional"))
    )
    (net (code "52") (name "/UART4_TX") (class "Default")
      (node (ref "J7") (pin "1") (pinfunction "1_1") (pintype "passive"))
      (node (ref "U1") (pin "14") (pinfunction "PA0_WKUP_14") (pintype "bidirectional"))
    )
    (net (code "53") (name "/UART5_RX") (class "Default")
      (node (ref "J1") (pin "7") (pinfunction "7_7") (pintype "passive"))
      (node (ref "U1") (pin "54") (pinfunction "PD2_54") (pintype "bidirectional"))
    )
    (net (code "54") (name "/UART5_TX") (class "Default")
      (node (ref "J1") (pin "5") (pinfunction "5_5") (pintype "passive"))
      (node (ref "U1") (pin "53") (pinfunction "PC12_53") (pintype "bidirectional"))
    )
    (net (code "55") (name "GND") (class "Default")
      (node (ref "C1") (pin "1") (pinfunction "1_1") (pintype "passive"))
      (node (ref "C10") (pin "1") (pinfunction "1_1") (pintype "passive"))
      (node (ref "C11") (pin "1") (pinfunction "1_1") (pintype "passive"))
      (node (ref "C17") (pin "1") (pinfunction "1_1") (pintype "passive"))
      (node (ref "C18") (pin "1") (pinfunction "1_1") (pintype "passive"))
      (node (ref "C19") (pin "1") (pinfunction "1_1") (pintype "passive"))
      (node (ref "C2") (pin "1") (pinfunction "1_1") (pintype "passive"))
      (node (ref "C22") (pin "1") (pinfunction "1_1") (pintype "passive"))
      (node (ref "C23") (pin "1") (pinfunction "1_1") (pintype "passive"))
      (node (ref "C24") (pin "1") (pinfunction "1_1") (pintype "passive"))
      (node (ref "C25") (pin "2") (pinfunction "2_2") (pintype "passive"))
      (node (ref "C26") (pin "1") (pinfunction "1_1") (pintype "passive"))
      (node (ref "C27") (pin "1") (pinfunction "1_1") (pintype "passive"))
      (node (ref "C28") (pin "1") (pinfunction "1_1") (pintype "passive"))
      (node (ref "C3") (pin "1") (pinfunction "1_1") (pintype "passive"))
      (node (ref "C4") (pin "1") (pinfunction "1_1") (pintype "passive"))
      (node (ref "C5") (pin "1") (pinfunction "1_1") (pintype "passive"))
      (node (ref "C6") (pin "1") (pinfunction "1_1") (pintype "passive"))
      (node (ref "C7") (pin "1") (pinfunction "1_1") (pintype "passive"))
      (node (ref "C8") (pin "2") (pinfunction "2_2") (pintype "passive"))
      (node (ref "C9") (pin "2") (pinfunction "2_2") (pintype "passive"))
      (node (ref "D1") (pin "2") (pinfunction "2_2") (pintype "power_in"))
      (node (ref "D2") (pin "1") (pinfunction "K2_1") (pintype "passive"))
      (node (ref "D3") (pin "1") (pinfunction "K2_1") (pintype "passive"))
      (node (ref "D4") (pin "1") (pinfunction "K2_1") (pintype "passive"))
      (node (ref "D5") (pin "2") (pinfunction "2_2") (pintype "power_in"))
      (node (ref "J1") (pin "3") (pinfunction "3_3") (pintype "passive"))
      (node (ref "J1") (pin "6") (pinfunction "6_6") (pintype "passive"))
      (node (ref "J10") (pin "1") (pinfunction "1_1") (pintype "passive"))
      (node (ref "J2") (pin "10") (pinfunction "10_10") (pintype "passive"))
      (node (ref "J2") (pin "11") (pinfunction "11_11") (pintype "passive"))
      (node (ref "J2") (pin "3") (pinfunction "3_3") (pintype "passive"))
      (node (ref "J2") (pin "4") (pinfunction "4_4") (pintype "passive"))
      (node (ref "J2") (pin "8") (pinfunction "8_8") (pintype "passive"))
      (node (ref "J2") (pin "MH1") (pinfunction "MH1_MH1") (pintype "passive"))
      (node (ref "J2") (pin "MH2") (pinfunction "MH2_MH2") (pintype "passive"))
      (node (ref "J3") (pin "2") (pinfunction "2_2") (pintype "passive"))
      (node (ref "J3") (pin "4") (pinfunction "4_4") (pintype "passive"))
      (node (ref "J4") (pin "4") (pinfunction "4_4") (pintype "passive"))
      (node (ref "J4") (pin "6") (pinfunction "6_6") (pintype "passive"))
      (node (ref "J5") (pin "4") (pinfunction "4_4") (pintype "passive"))
      (node (ref "J5") (pin "6") (pinfunction "6_6") (pintype "passive"))
      (node (ref "J5") (pin "8") (pinfunction "8_8") (pintype "passive"))
      (node (ref "J8") (pin "6") (pinfunction "6_6") (pintype "passive"))
      (node (ref "J9") (pin "2") (pinfunction "2_2") (pintype "passive"))
      (node (ref "LS") (pin "2") (pinfunction "2_2") (pintype "passive"))
      (node (ref "R15") (pin "1") (pinfunction "1_1") (pintype "passive"))
      (node (ref "R16") (pin "1") (pinfunction "1_1") (pintype "passive"))
      (node (ref "R17") (pin "1") (pinfunction "1_1") (pintype "passive"))
      (node (ref "R18") (pin "1") (pinfunction "1_1") (pintype "passive"))
      (node (ref "R2") (pin "1") (pinfunction "1_1") (pintype "passive"))
      (node (ref "R6") (pin "1") (pinfunction "1_1") (pintype "passive"))
      (node (ref "R8") (pin "2") (pinfunction "2_2") (pintype "passive"))
      (node (ref "U1") (pin "12") (pinfunction "VSSA_12") (pintype "power_in"))
      (node (ref "U1") (pin "18") (pinfunction "VSS_18") (pintype "power_in"))
      (node (ref "U1") (pin "60") (pinfunction "BOOT0_60") (pintype "input"))
      (node (ref "U1") (pin "63") (pinfunction "VSS_63") (pintype "power_in"))
      (node (ref "U3") (pin "14") (pinfunction "RES_14") (pintype "passive"))
      (node (ref "U3") (pin "15") (pinfunction "RES_15") (pintype "passive"))
      (node (ref "U3") (pin "16") (pinfunction "RES_16") (pintype "passive"))
      (node (ref "U3") (pin "17") (pinfunction "RES_17") (pintype "passive"))
      (node (ref "U3") (pin "18") (pinfunction "RES_18") (pintype "passive"))
      (node (ref "U3") (pin "19") (pinfunction "GND_19") (pintype "power_in"))
      (node (ref "U3") (pin "20") (pinfunction "GND_20") (pintype "power_in"))
      (node (ref "U4") (pin "13") (pinfunction "MODE_13") (pintype "input"))
      (node (ref "U4") (pin "14") (pinfunction "F_14") (pintype "input"))
      (node (ref "U4") (pin "8") (pinfunction "VSS_8") (pintype "power_in"))
      (node (ref "U5") (pin "2") (pinfunction "PS_2") (pintype "passive"))
      (node (ref "U5") (pin "3") (pinfunction "GND_3") (pintype "passive"))
      (node (ref "U6") (pin "4") (pinfunction "GND_4") (pintype "power_in"))
    )
    (net (code "56") (name "MAINBAT") (class "Default")
      (node (ref "D5") (pin "1") (pinfunction "1_1") (pintype "power_in"))
      (node (ref "J2") (pin "1") (pinfunction "1_1") (pintype "passive"))
      (node (ref "R1") (pin "2") (pinfunction "2_2") (pintype "passive"))
    )
    (net (code "57") (name "Net-(D2-A2)") (class "Default")
      (node (ref "D2") (pin "2") (pinfunction "A2_2") (pintype "passive"))
      (node (ref "R3") (pin "1") (pinfunction "1_1") (pintype "passive"))
    )
    (net (code "58") (name "Net-(D3-A2)") (class "Default")
      (node (ref "D3") (pin "2") (pinfunction "A2_2") (pintype "passive"))
      (node (ref "R4") (pin "1") (pinfunction "1_1") (pintype "passive"))
    )
    (net (code "59") (name "Net-(D4-A2)") (class "Default")
      (node (ref "D4") (pin "2") (pinfunction "A2_2") (pintype "passive"))
      (node (ref "R5") (pin "1") (pinfunction "1_1") (pintype "passive"))
    )
    (net (code "60") (name "Net-(F1-Pad2)") (class "Default")
      (node (ref "F1") (pin "2") (pinfunction "2_2") (pintype "passive"))
      (node (ref "J2") (pin "12") (pinfunction "12_12") (pintype "passive"))
      (node (ref "J2") (pin "13") (pinfunction "13_13") (pintype "passive"))
      (node (ref "J2") (pin "14") (pinfunction "14_14") (pintype "passive"))
    )
    (net (code "61") (name "Net-(F2-Pad2)") (class "Default")
      (node (ref "F2") (pin "2") (pinfunction "2_2") (pintype "passive"))
      (node (ref "J3") (pin "1") (pinfunction "1_1") (pintype "passive"))
      (node (ref "J3") (pin "3") (pinfunction "3_3") (pintype "passive"))
    )
    (net (code "62") (name "Net-(LS-Pad1)") (class "Default")
      (node (ref "LS") (pin "1") (pinfunction "1_1") (pintype "passive"))
      (node (ref "R7") (pin "2") (pinfunction "2_2") (pintype "passive"))
      (node (ref "R8") (pin "1") (pinfunction "1_1") (pintype "passive"))
    )
    (net (code "63") (name "Net-(U1B-PC0)") (class "Default")
      (node (ref "R1") (pin "1") (pinfunction "1_1") (pintype "passive"))
      (node (ref "R2") (pin "2") (pinfunction "2_2") (pintype "passive"))
      (node (ref "U1") (pin "8") (pinfunction "PC0_8") (pintype "bidirectional"))
    )
    (net (code "64") (name "Net-(U1B-PH0{slash}OSC_IN)") (class "Default")
      (node (ref "C8") (pin "1") (pinfunction "1_1") (pintype "passive"))
      (node (ref "U1") (pin "5") (pinfunction "PH0/OSC_IN_5") (pintype "bidirectional"))
      (node (ref "Y1") (pin "2") (pinfunction "2_2") (pintype "power_in"))
    )
    (net (code "65") (name "Net-(U1B-PH1{slash}OSC_OUT)") (class "Default")
      (node (ref "C9") (pin "1") (pinfunction "1_1") (pintype "passive"))
      (node (ref "U1") (pin "6") (pinfunction "PH1/OSC_OUT_6") (pintype "bidirectional"))
      (node (ref "Y1") (pin "1") (pinfunction "1_1") (pintype "power_in"))
    )
    (net (code "66") (name "Net-(U1B-VCAP_1)") (class "Default")
      (node (ref "C10") (pin "2") (pinfunction "2_2") (pintype "passive"))
      (node (ref "U1") (pin "31") (pinfunction "VCAP_1_31") (pintype "power_in"))
    )
    (net (code "67") (name "Net-(U1B-VCAP_2)") (class "Default")
      (node (ref "C11") (pin "2") (pinfunction "2_2") (pintype "passive"))
      (node (ref "U1") (pin "47") (pinfunction "VCAP_2_47") (pintype "power_in"))
    )
    (net (code "68") (name "Net-(U3-C1)") (class "Default")
      (node (ref "C18") (pin "2") (pinfunction "2_2") (pintype "passive"))
      (node (ref "U3") (pin "24") (pinfunction "C1_24") (pintype "passive"))
    )
    (net (code "69") (name "Net-(U3-CAP)") (class "Default")
      (node (ref "C19") (pin "2") (pinfunction "2_2") (pintype "passive"))
      (node (ref "U3") (pin "21") (pinfunction "CAP_21") (pintype "passive"))
    )
    (net (code "70") (name "Net-(U6-~{HOLD{slash}RESET!(IO3)})") (class "Default")
      (node (ref "R19") (pin "1") (pinfunction "1_1") (pintype "passive"))
      (node (ref "U6") (pin "7") (pinfunction "~{HOLD/RESET!(IO3)}_7") (pintype "bidirectional"))
    )
    (net (code "71") (name "unconnected-(J4-Pad2)") (class "Default")
      (node (ref "J4") (pin "2") (pinfunction "2_2") (pintype "passive"))
    )
    (net (code "72") (name "unconnected-(J7-Pad3)") (class "Default")
      (node (ref "J7") (pin "3") (pinfunction "3_3") (pintype "passive"))
    )
    (net (code "73") (name "unconnected-(J7-Pad4)") (class "Default")
      (node (ref "J7") (pin "4") (pinfunction "4_4") (pintype "passive"))
    )
    (net (code "74") (name "unconnected-(J7-Pad5)") (class "Default")
      (node (ref "J7") (pin "5") (pinfunction "5_5") (pintype "passive"))
    )
    (net (code "75") (name "unconnected-(J7-Pad6)") (class "Default")
      (node (ref "J7") (pin "6") (pinfunction "6_6") (pintype "passive"))
    )
    (net (code "76") (name "unconnected-(J8-Pad1)") (class "Default")
      (node (ref "J8") (pin "1") (pinfunction "1_1") (pintype "passive"))
    )
    (net (code "77") (name "unconnected-(J8-Pad2)") (class "Default")
      (node (ref "J8") (pin "2") (pinfunction "2_2") (pintype "passive"))
    )
    (net (code "78") (name "unconnected-(J8-Pad3)") (class "Default")
      (node (ref "J8") (pin "3") (pinfunction "3_3") (pintype "passive"))
    )
    (net (code "79") (name "unconnected-(J8-Pad4)") (class "Default")
      (node (ref "J8") (pin "4") (pinfunction "4_4") (pintype "passive"))
    )
    (net (code "80") (name "unconnected-(U1B-PA11-Pad44)") (class "Default")
      (node (ref "U1") (pin "44") (pinfunction "PA11_44") (pintype "bidirectional"))
    )
    (net (code "81") (name "unconnected-(U1B-PA12-Pad45)") (class "Default")
      (node (ref "U1") (pin "45") (pinfunction "PA12_45") (pintype "bidirectional"))
    )
    (net (code "82") (name "unconnected-(U1B-PB8-Pad61)") (class "Default")
      (node (ref "U1") (pin "61") (pinfunction "PB8_61") (pintype "bidirectional"))
    )
    (net (code "83") (name "unconnected-(U1B-PB9-Pad62)") (class "Default")
      (node (ref "U1") (pin "62") (pinfunction "PB9_62") (pintype "bidirectional"))
    )
    (net (code "84") (name "unconnected-(U1B-PB12-Pad33)") (class "Default")
      (node (ref "U1") (pin "33") (pinfunction "PB12_33") (pintype "bidirectional"))
    )
    (net (code "85") (name "unconnected-(U1B-PC1-Pad9)") (class "Default")
      (node (ref "U1") (pin "9") (pinfunction "PC1_9") (pintype "bidirectional"))
    )
    (net (code "86") (name "unconnected-(U1B-PC13-Pad2)") (class "Default")
      (node (ref "U1") (pin "2") (pinfunction "PC13_2") (pintype "bidirectional"))
    )
    (net (code "87") (name "unconnected-(U1B-PC15{slash}OSC32_OUT-Pad4)") (class "Default")
      (node (ref "U1") (pin "4") (pinfunction "PC15/OSC32_OUT_4") (pintype "bidirectional"))
    )
    (net (code "88") (name "unconnected-(U3-DEN_A{slash}G-Pad13)") (class "Default")
      (node (ref "U3") (pin "13") (pinfunction "DEN_A/G_13") (pintype "passive+no_connect"))
    )
    (net (code "89") (name "unconnected-(U3-DRDY_M-Pad9)") (class "Default")
      (node (ref "U3") (pin "9") (pinfunction "DRDY_M_9") (pintype "passive+no_connect"))
    )
    (net (code "90") (name "unconnected-(U3-INT1_A{slash}G-Pad11)") (class "Default")
      (node (ref "U3") (pin "11") (pinfunction "INT1_A/G_11") (pintype "passive+no_connect"))
    )
    (net (code "91") (name "unconnected-(U3-INT2_A{slash}G-Pad12)") (class "Default")
      (node (ref "U3") (pin "12") (pinfunction "INT2_A/G_12") (pintype "passive+no_connect"))
    )
    (net (code "92") (name "unconnected-(U3-INT_M-Pad10)") (class "Default")
      (node (ref "U3") (pin "10") (pinfunction "INT_M_10") (pintype "passive+no_connect"))
    )
    (net (code "93") (name "unconnected-(U4-L-Pad15)") (class "Default")
      (node (ref "U4") (pin "15") (pinfunction "L_15") (pintype "output+no_connect"))
    )
  )
)
